# USB.net
KiCad netlist of a schematic drawn in Altium Designer
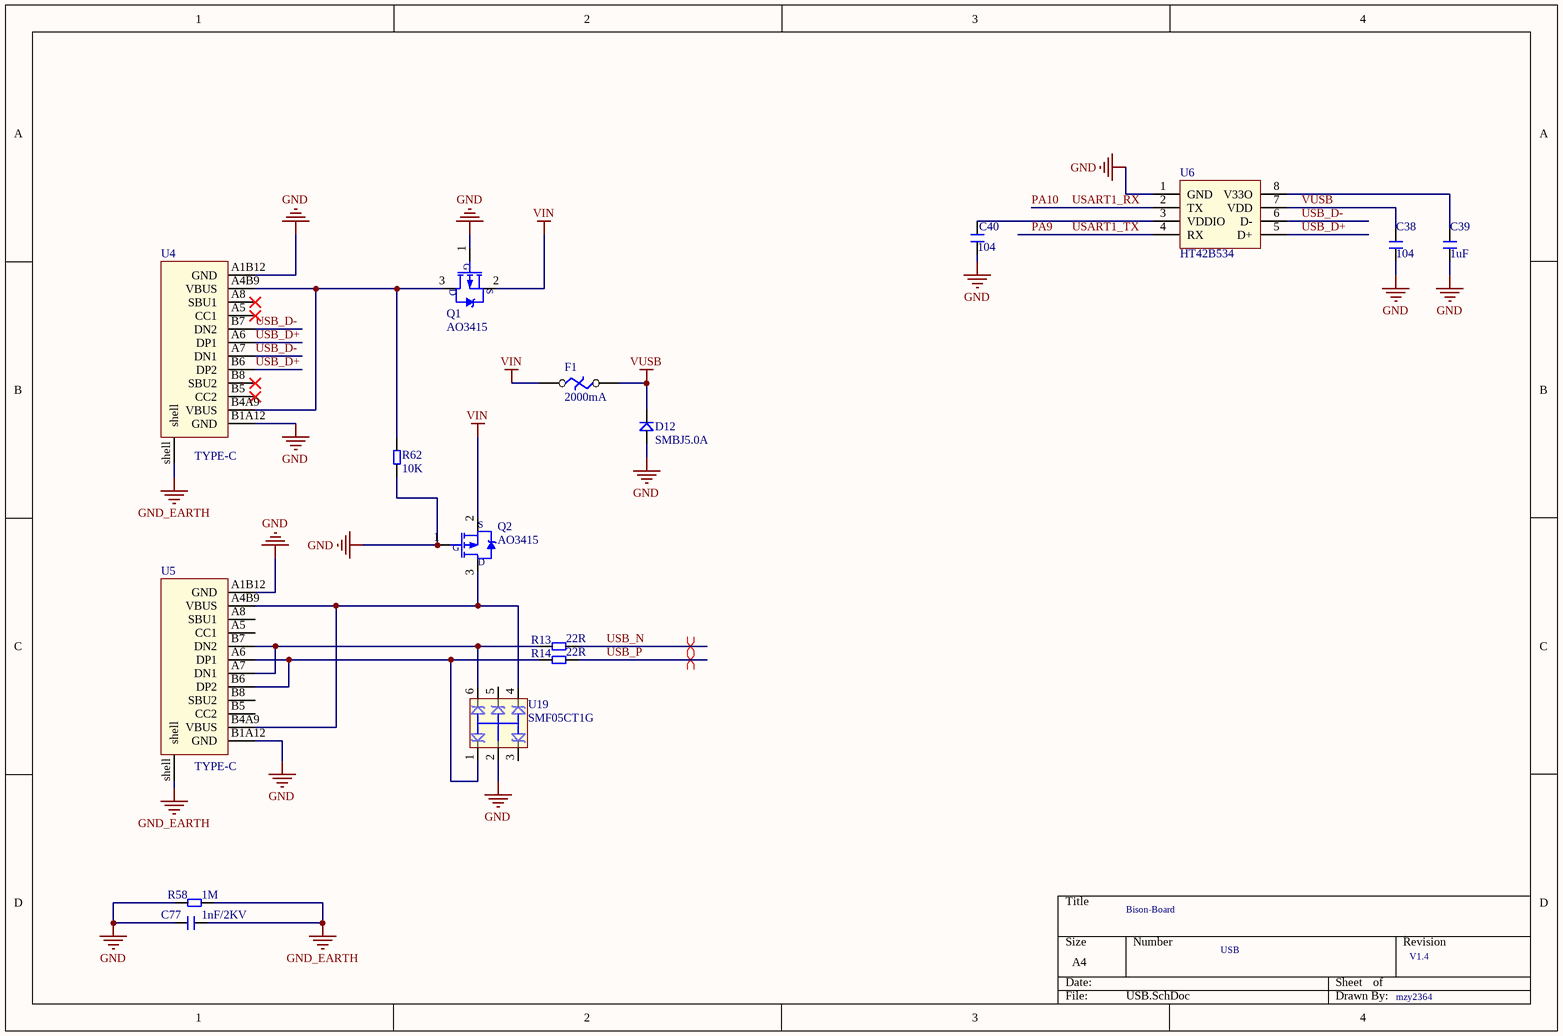
[diagram p0: USB.SchDoc]

(export (version "E")
  (design (tool "Eeschema 10.0.6"))
  (components
    (comp (ref "C38") (value "104") (footprint "C 0603") (libsource (lib "松鼠GUI原理图库") (part "CAP")))
    (comp (ref "C39") (value "1uF") (footprint "C 0603") (libsource (lib "松鼠GUI原理图库") (part "CAP")))
    (comp (ref "C40") (value "104") (footprint "C 0603") (libsource (lib "松鼠GUI原理图库") (part "CAP")))
    (comp (ref "C77") (value "1nF/2KV") (footprint "C 1206") (libsource (lib "Bison-Board") (part "CAP")))
    (comp (ref "D12") (value "SMBJ5.0A") (footprint "SMA") (libsource (lib "Bison-Board") (part "Diode")))
    (comp (ref "F1")
      (value "2000mA")
      (footprint "F 0805")
      (description "熔断开关")
      (libsource (lib "松鼠GUI原理图库") (part "F"))
    )
    (comp (ref "Q1") (value "AO3415") (footprint "SOT23-3") (libsource (lib "squ-guiboard") (part "PMOS-2")))
    (comp (ref "Q2") (value "AO3415") (footprint "SOT23-3") (libsource (lib "squ-guiboard") (part "PMOS-2")))
    (comp (ref "R13") (value "22R") (footprint "R 0603") (libsource (lib "松鼠GUI原理图库") (part "RES")))
    (comp (ref "R14") (value "22R") (footprint "R 0603") (libsource (lib "松鼠GUI原理图库") (part "RES")))
    (comp (ref "R58") (value "1M") (footprint "R 1206") (libsource (lib "Bison-Board") (part "RES")))
    (comp (ref "R62") (value "10K") (footprint "R 0603") (libsource (lib "松鼠GUI原理图库") (part "RES")))
    (comp (ref "U4")
      (value "TYPE-C")
      (footprint "USB-TYPE-C")
      (description "TYPE-C 16pin")
      (libsource (lib "Bison-Board") (part "USB TYPE-C"))
    )
    (comp (ref "U5")
      (value "TYPE-C")
      (footprint "USB-TYPE-C")
      (description "TYPE-C 16pin")
      (libsource (lib "Bison-Board") (part "USB TYPE-C"))
    )
    (comp (ref "U6")
      (value "HT42B534")
      (footprint "SOP8")
      (description "USB转串口")
      (libsource (lib "松鼠GUI原理图库") (part "HT42B534"))
    )
    (comp (ref "U19")
      (value "SMF05CT1G")
      (footprint "SOT363")
      (description "TVS")
      (libsource (lib "Bison-Board") (part "SMF05CT1G"))
    )
  )
  (nets
    (net (code "1") (name "/PA9") (class "Default")
      (node (ref "U6") (pin "4") (pinfunction "RX_4") (pintype "passive"))
    )
    (net (code "2") (name "/PA10") (class "Default")
      (node (ref "U6") (pin "2") (pinfunction "TX_2") (pintype "passive"))
    )
    (net (code "3") (name "/USB_D+") (class "Default")
      (node (ref "U4") (pin "A6") (pinfunction "DP1_A6") (pintype "passive"))
      (node (ref "U4") (pin "B6") (pinfunction "DP2_B6") (pintype "passive"))
      (node (ref "U6") (pin "5") (pinfunction "D+_5") (pintype "passive"))
    )
    (net (code "4") (name "/USB_D-") (class "Default")
      (node (ref "U4") (pin "A7") (pinfunction "DN1_A7") (pintype "passive"))
      (node (ref "U4") (pin "B7") (pinfunction "DN2_B7") (pintype "passive"))
      (node (ref "U6") (pin "6") (pinfunction "D-_6") (pintype "passive"))
    )
    (net (code "5") (name "/USB_N") (class "Default") (node (ref "R13") (pin "2") (pintype "passive")))
    (net (code "6") (name "/USB_P") (class "Default") (node (ref "R14") (pin "2") (pintype "passive")))
    (net (code "7") (name "GND") (class "Default")
      (node (ref "C38") (pin "1") (pinfunction "1_1") (pintype "passive"))
      (node (ref "C39") (pin "2") (pinfunction "2_2") (pintype "passive"))
      (node (ref "C40") (pin "1") (pinfunction "1_1") (pintype "passive"))
      (node (ref "C77") (pin "1") (pinfunction "1_1") (pintype "passive"))
      (node (ref "D12") (pin "1") (pintype "passive"))
      (node (ref "Q1") (pin "1") (pinfunction "G_1") (pintype "passive"))
      (node (ref "Q2") (pin "1") (pinfunction "G_1") (pintype "passive"))
      (node (ref "R58") (pin "1") (pintype "passive"))
      (node (ref "R62") (pin "1") (pintype "passive"))
      (node (ref "U19") (pin "2") (pinfunction "2_2") (pintype "passive"))
      (node (ref "U4") (pin "A1B12") (pinfunction "GND_A1B12") (pintype "passive"))
      (node (ref "U4") (pin "B1A12") (pinfunction "GND_B1A12") (pintype "passive"))
      (node (ref "U5") (pin "A1B12") (pinfunction "GND_A1B12") (pintype "passive"))
      (node (ref "U5") (pin "B1A12") (pinfunction "GND_B1A12") (pintype "passive"))
      (node (ref "U6") (pin "1") (pinfunction "GND_1") (pintype "passive"))
    )
    (net (code "8") (name "GND_EARTH") (class "Default")
      (node (ref "C77") (pin "2") (pinfunction "2_2") (pintype "passive"))
      (node (ref "R58") (pin "2") (pintype "passive"))
      (node (ref "U4") (pin "shell") (pinfunction "shell_shell") (pintype "passive"))
      (node (ref "U5") (pin "shell") (pinfunction "shell_shell") (pintype "passive"))
    )
    (net (code "9") (name "Net-(Q1-D)") (class "Default")
      (node (ref "Q1") (pin "3") (pinfunction "D_3") (pintype "passive"))
      (node (ref "R62") (pin "2") (pintype "passive"))
      (node (ref "U4") (pin "A4B9") (pinfunction "VBUS_A4B9") (pintype "passive"))
      (node (ref "U4") (pin "B4A9") (pinfunction "VBUS_B4A9") (pintype "passive"))
    )
    (net (code "10") (name "Net-(Q2-D)") (class "Default")
      (node (ref "Q2") (pin "3") (pinfunction "D_3") (pintype "passive"))
      (node (ref "U19") (pin "4") (pinfunction "4_4") (pintype "passive"))
      (node (ref "U5") (pin "A4B9") (pinfunction "VBUS_A4B9") (pintype "passive"))
      (node (ref "U5") (pin "B4A9") (pinfunction "VBUS_B4A9") (pintype "passive"))
    )
    (net (code "11") (name "Net-(U5-DN1)") (class "Default")
      (node (ref "R13") (pin "1") (pintype "passive"))
      (node (ref "U19") (pin "6") (pinfunction "6_6") (pintype "passive"))
      (node (ref "U5") (pin "A7") (pinfunction "DN1_A7") (pintype "passive"))
      (node (ref "U5") (pin "B7") (pinfunction "DN2_B7") (pintype "passive"))
    )
    (net (code "12") (name "Net-(U5-DP1)") (class "Default")
      (node (ref "R14") (pin "1") (pintype "passive"))
      (node (ref "U19") (pin "1") (pinfunction "1_1") (pintype "passive"))
      (node (ref "U5") (pin "A6") (pinfunction "DP1_A6") (pintype "passive"))
      (node (ref "U5") (pin "B6") (pinfunction "DP2_B6") (pintype "passive"))
    )
    (net (code "13") (name "Net-(U6-V33O)") (class "Default")
      (node (ref "C39") (pin "1") (pinfunction "1_1") (pintype "passive"))
      (node (ref "U6") (pin "8") (pinfunction "V33O_8") (pintype "passive"))
    )
    (net (code "14") (name "Net-(U6-VDDIO)") (class "Default")
      (node (ref "C40") (pin "2") (pinfunction "2_2") (pintype "passive"))
      (node (ref "U6") (pin "3") (pinfunction "VDDIO_3") (pintype "passive"))
    )
    (net (code "15") (name "VIN") (class "Default")
      (node (ref "F1") (pin "1") (pinfunction "1_1") (pintype "passive"))
      (node (ref "Q1") (pin "2") (pinfunction "S_2") (pintype "passive"))
      (node (ref "Q2") (pin "2") (pinfunction "S_2") (pintype "passive"))
    )
    (net (code "16") (name "VUSB") (class "Default")
      (node (ref "C38") (pin "2") (pinfunction "2_2") (pintype "passive"))
      (node (ref "D12") (pin "2") (pintype "passive"))
      (node (ref "F1") (pin "2") (pinfunction "2_2") (pintype "passive"))
      (node (ref "U6") (pin "7") (pinfunction "VDD_7") (pintype "passive"))
    )
    (net (code "17") (name "unconnected-(U4-CC1-PadA5)") (class "Default")
      (node (ref "U4") (pin "A5") (pinfunction "CC1_A5") (pintype "passive+no_connect"))
    )
    (net (code "18") (name "unconnected-(U4-CC2-PadB5)") (class "Default")
      (node (ref "U4") (pin "B5") (pinfunction "CC2_B5") (pintype "passive+no_connect"))
    )
    (net (code "19") (name "unconnected-(U4-SBU1-PadA8)") (class "Default")
      (node (ref "U4") (pin "A8") (pinfunction "SBU1_A8") (pintype "passive+no_connect"))
    )
    (net (code "20") (name "unconnected-(U4-SBU2-PadB8)") (class "Default")
      (node (ref "U4") (pin "B8") (pinfunction "SBU2_B8") (pintype "passive+no_connect"))
    )
    (net (code "21") (name "unconnected-(U5-CC1-PadA5)") (class "Default")
      (node (ref "U5") (pin "A5") (pinfunction "CC1_A5") (pintype "passive"))
    )
    (net (code "22") (name "unconnected-(U5-CC2-PadB5)") (class "Default")
      (node (ref "U5") (pin "B5") (pinfunction "CC2_B5") (pintype "passive"))
    )
    (net (code "23") (name "unconnected-(U5-SBU1-PadA8)") (class "Default")
      (node (ref "U5") (pin "A8") (pinfunction "SBU1_A8") (pintype "passive"))
    )
    (net (code "24") (name "unconnected-(U5-SBU2-PadB8)") (class "Default")
      (node (ref "U5") (pin "B8") (pinfunction "SBU2_B8") (pintype "passive"))
    )
    (net (code "25") (name "unconnected-(U19-Pad3)") (class "Default")
      (node (ref "U19") (pin "3") (pinfunction "3_3") (pintype "passive"))
    )
    (net (code "26") (name "unconnected-(U19-Pad5)") (class "Default")
      (node (ref "U19") (pin "5") (pinfunction "5_5") (pintype "passive"))
    )
  )
)
